# RamaTA.net
KiCad netlist of a schematic drawn in EAGLE
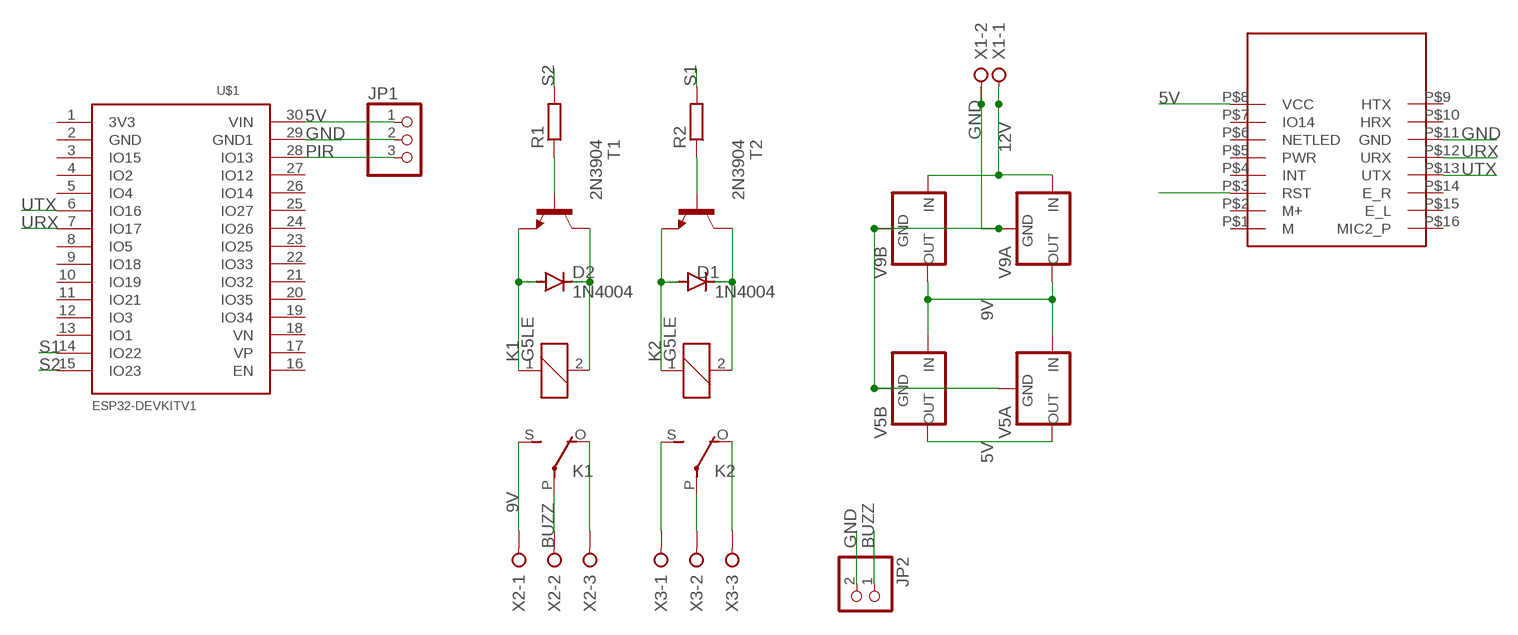
[diagram p0: schematic, sheet 1]

(export (version "E")
  (design (tool "Eeschema 10.0.6"))
  (components
    (comp (ref "D1")
      (value "1N4004")
      (footprint "eagle-import:DO41-10")
      (libsource (lib "eagle-import") (part "1N4004"))
    )
    (comp (ref "D2")
      (value "1N4004")
      (footprint "eagle-import:DO41-10")
      (libsource (lib "eagle-import") (part "1N4004"))
    )
    (comp (ref "JP1")
      (value "PINHD-1X3")
      (footprint "eagle-import:1X03")
      (libsource (lib "eagle-import") (part "PINHD-1X3"))
    )
    (comp (ref "JP2")
      (value "PINHD-1X2")
      (footprint "eagle-import:1X02")
      (libsource (lib "eagle-import") (part "PINHD-1X2"))
    )
    (comp (ref "K1")
      (value "G5LE")
      (footprint "eagle-import:G5LE")
      (libsource (lib "eagle-import") (part "G5LE"))
    )
    (comp (ref "K2")
      (value "G5LE")
      (footprint "eagle-import:G5LE")
      (libsource (lib "eagle-import") (part "G5LE"))
    )
    (comp (ref "R1")
      (value "R-EU_0207/10")
      (footprint "eagle-import:0207_10")
      (libsource (lib "eagle-import") (part "R-EU_0207/10"))
    )
    (comp (ref "R2")
      (value "R-EU_0207/10")
      (footprint "eagle-import:0207_10")
      (libsource (lib "eagle-import") (part "R-EU_0207/10"))
    )
    (comp (ref "T1")
      (value "2N3904")
      (footprint "eagle-import:TO92")
      (libsource (lib "eagle-import") (part "2N3904"))
    )
    (comp (ref "T2")
      (value "2N3904")
      (footprint "eagle-import:TO92")
      (libsource (lib "eagle-import") (part "2N3904"))
    )
    (comp (ref "U$1")
      (value "ESP32DEVKITV1")
      (footprint "eagle-import:ESP32-DEVKITV1")
      (libsource (lib "eagle-import") (part "ESP32DEVKITV1"))
    )
    (comp (ref "U$7")
      (value "SIM_A6SIM_GA6")
      (footprint "eagle-import:SIM_GA6")
      (libsource (lib "eagle-import") (part "SIM_A6SIM_GA6"))
    )
    (comp (ref "V5A")
      (value "78XXS")
      (footprint "eagle-import:78XXS")
      (libsource (lib "eagle-import") (part "78XXS"))
    )
    (comp (ref "V5B")
      (value "78XXS")
      (footprint "eagle-import:78XXS")
      (libsource (lib "eagle-import") (part "78XXS"))
    )
    (comp (ref "V9A")
      (value "78XXS")
      (footprint "eagle-import:78XXS")
      (libsource (lib "eagle-import") (part "78XXS"))
    )
    (comp (ref "V9B")
      (value "78XXS")
      (footprint "eagle-import:78XXS")
      (libsource (lib "eagle-import") (part "78XXS"))
    )
    (comp (ref "X1")
      (value "W237-02P")
      (footprint "eagle-import:W237-2")
      (libsource (lib "eagle-import") (part "W237-02P"))
    )
    (comp (ref "X2")
      (value "W237-03P")
      (footprint "eagle-import:W237-3")
      (libsource (lib "eagle-import") (part "W237-03P"))
    )
    (comp (ref "X3")
      (value "W237-03P")
      (footprint "eagle-import:W237-3")
      (libsource (lib "eagle-import") (part "W237-03P"))
    )
  )
  (nets
    (net (code "1") (name "/5V") (class "Default")
      (node (ref "JP1") (pin "1") (pinfunction "1_1") (pintype "passive"))
      (node (ref "U$1") (pin "30") (pinfunction "VIN_30") (pintype "bidirectional"))
      (node (ref "U$7") (pin "P$8") (pinfunction "VCC_P$8") (pintype "bidirectional"))
      (node (ref "V5A") (pin "OUT") (pinfunction "OUT_OUT") (pintype "passive"))
      (node (ref "V5B") (pin "OUT") (pinfunction "OUT_OUT") (pintype "passive"))
    )
    (net (code "2") (name "/9V") (class "Default")
      (node (ref "K1") (pin "S") (pinfunction "S_S") (pintype "passive"))
      (node (ref "V5A") (pin "IN") (pinfunction "IN_IN") (pintype "input"))
      (node (ref "V5B") (pin "IN") (pinfunction "IN_IN") (pintype "input"))
      (node (ref "V9A") (pin "OUT") (pinfunction "OUT_OUT") (pintype "passive"))
      (node (ref "V9B") (pin "OUT") (pinfunction "OUT_OUT") (pintype "passive"))
      (node (ref "X2") (pin "1") (pinfunction "KL_1") (pintype "passive"))
    )
    (net (code "3") (name "/12V") (class "Default")
      (node (ref "V9A") (pin "IN") (pinfunction "IN_IN") (pintype "input"))
      (node (ref "V9B") (pin "IN") (pinfunction "IN_IN") (pintype "input"))
      (node (ref "X1") (pin "1") (pinfunction "KL_1") (pintype "passive"))
    )
    (net (code "4") (name "/BUZZ") (class "Default")
      (node (ref "JP2") (pin "1") (pinfunction "1_1") (pintype "passive"))
      (node (ref "K1") (pin "P") (pinfunction "P_P") (pintype "passive"))
      (node (ref "X2") (pin "2") (pinfunction "KL_2") (pintype "passive"))
    )
    (net (code "5") (name "/GND") (class "Default")
      (node (ref "JP1") (pin "2") (pinfunction "2_2") (pintype "passive"))
      (node (ref "JP2") (pin "2") (pinfunction "2_2") (pintype "passive"))
      (node (ref "U$1") (pin "29") (pinfunction "GND1_29") (pintype "bidirectional"))
      (node (ref "U$7") (pin "P$11") (pinfunction "GND_P$11") (pintype "bidirectional"))
      (node (ref "V5A") (pin "GND") (pinfunction "GND_GND") (pintype "input"))
      (node (ref "V5B") (pin "GND") (pinfunction "GND_GND") (pintype "input"))
      (node (ref "V9A") (pin "GND") (pinfunction "GND_GND") (pintype "input"))
      (node (ref "V9B") (pin "GND") (pinfunction "GND_GND") (pintype "input"))
      (node (ref "X1") (pin "2") (pinfunction "KL_2") (pintype "passive"))
    )
    (net (code "6") (name "/PIR") (class "Default")
      (node (ref "JP1") (pin "3") (pinfunction "3_3") (pintype "passive"))
      (node (ref "U$1") (pin "28") (pinfunction "IO13_28") (pintype "bidirectional"))
    )
    (net (code "7") (name "/S1") (class "Default")
      (node (ref "R2") (pin "2") (pinfunction "2_2") (pintype "passive"))
      (node (ref "U$1") (pin "14") (pinfunction "IO22_14") (pintype "bidirectional"))
    )
    (net (code "8") (name "/S2") (class "Default")
      (node (ref "R1") (pin "2") (pinfunction "2_2") (pintype "passive"))
      (node (ref "U$1") (pin "15") (pinfunction "IO23_15") (pintype "bidirectional"))
    )
    (net (code "9") (name "/URX") (class "Default")
      (node (ref "U$1") (pin "7") (pinfunction "IO17_7") (pintype "bidirectional"))
      (node (ref "U$7") (pin "P$12") (pinfunction "URX_P$12") (pintype "bidirectional"))
    )
    (net (code "10") (name "/UTX") (class "Default")
      (node (ref "U$1") (pin "6") (pinfunction "IO16_6") (pintype "bidirectional"))
      (node (ref "U$7") (pin "P$13") (pinfunction "UTX_P$13") (pintype "bidirectional"))
    )
    (net (code "11") (name "Net-(T1-B)") (class "Default")
      (node (ref "R1") (pin "1") (pinfunction "1_1") (pintype "passive"))
      (node (ref "T1") (pin "2") (pinfunction "B_2") (pintype "passive"))
    )
    (net (code "12") (name "Net-(T1-C)") (class "Default")
      (node (ref "D2") (pin "C") (pinfunction "C_C") (pintype "passive"))
      (node (ref "K1") (pin "2") (pinfunction "2_2") (pintype "passive"))
      (node (ref "T1") (pin "1") (pinfunction "C_1") (pintype "passive"))
    )
    (net (code "13") (name "Net-(T1-E)") (class "Default")
      (node (ref "D2") (pin "A") (pinfunction "A_A") (pintype "passive"))
      (node (ref "K1") (pin "1") (pinfunction "1_1") (pintype "passive"))
      (node (ref "T1") (pin "3") (pinfunction "E_3") (pintype "passive"))
    )
    (net (code "14") (name "Net-(T2-B)") (class "Default")
      (node (ref "R2") (pin "1") (pinfunction "1_1") (pintype "passive"))
      (node (ref "T2") (pin "2") (pinfunction "B_2") (pintype "passive"))
    )
    (net (code "15") (name "Net-(T2-C)") (class "Default")
      (node (ref "D1") (pin "C") (pinfunction "C_C") (pintype "passive"))
      (node (ref "K2") (pin "2") (pinfunction "2_2") (pintype "passive"))
      (node (ref "T2") (pin "1") (pinfunction "C_1") (pintype "passive"))
    )
    (net (code "16") (name "Net-(T2-E)") (class "Default")
      (node (ref "D1") (pin "A") (pinfunction "A_A") (pintype "passive"))
      (node (ref "K2") (pin "1") (pinfunction "1_1") (pintype "passive"))
      (node (ref "T2") (pin "3") (pinfunction "E_3") (pintype "passive"))
    )
    (net (code "17") (name "Net-(X2C-KL)") (class "Default")
      (node (ref "K1") (pin "O") (pinfunction "O_O") (pintype "passive"))
      (node (ref "X2") (pin "3") (pinfunction "KL_3") (pintype "passive"))
    )
    (net (code "18") (name "Net-(X3A-KL)") (class "Default")
      (node (ref "K2") (pin "S") (pinfunction "S_S") (pintype "passive"))
      (node (ref "X3") (pin "1") (pinfunction "KL_1") (pintype "passive"))
    )
    (net (code "19") (name "Net-(X3B-KL)") (class "Default")
      (node (ref "K2") (pin "P") (pinfunction "P_P") (pintype "passive"))
      (node (ref "X3") (pin "2") (pinfunction "KL_2") (pintype "passive"))
    )
    (net (code "20") (name "Net-(X3C-KL)") (class "Default")
      (node (ref "K2") (pin "O") (pinfunction "O_O") (pintype "passive"))
      (node (ref "X3") (pin "3") (pinfunction "KL_3") (pintype "passive"))
    )
    (net (code "21") (name "unconnected-(U$1-3V3-Pad1)") (class "Default")
      (node (ref "U$1") (pin "1") (pinfunction "3V3_1") (pintype "bidirectional"))
    )
    (net (code "22") (name "unconnected-(U$1-EN-Pad16)") (class "Default")
      (node (ref "U$1") (pin "16") (pinfunction "EN_16") (pintype "bidirectional"))
    )
    (net (code "23") (name "unconnected-(U$1-GND-Pad2)") (class "Default")
      (node (ref "U$1") (pin "2") (pinfunction "GND_2") (pintype "bidirectional"))
    )
    (net (code "24") (name "unconnected-(U$1-IO1-Pad13)") (class "Default")
      (node (ref "U$1") (pin "13") (pinfunction "IO1_13") (pintype "bidirectional"))
    )
    (net (code "25") (name "unconnected-(U$1-IO2-Pad4)") (class "Default")
      (node (ref "U$1") (pin "4") (pinfunction "IO2_4") (pintype "bidirectional"))
    )
    (net (code "26") (name "unconnected-(U$1-IO3-Pad12)") (class "Default")
      (node (ref "U$1") (pin "12") (pinfunction "IO3_12") (pintype "bidirectional"))
    )
    (net (code "27") (name "unconnected-(U$1-IO4-Pad5)") (class "Default")
      (node (ref "U$1") (pin "5") (pinfunction "IO4_5") (pintype "bidirectional"))
    )
    (net (code "28") (name "unconnected-(U$1-IO5-Pad8)") (class "Default")
      (node (ref "U$1") (pin "8") (pinfunction "IO5_8") (pintype "bidirectional"))
    )
    (net (code "29") (name "unconnected-(U$1-IO12-Pad27)") (class "Default")
      (node (ref "U$1") (pin "27") (pinfunction "IO12_27") (pintype "bidirectional"))
    )
    (net (code "30") (name "unconnected-(U$1-IO14-Pad26)") (class "Default")
      (node (ref "U$1") (pin "26") (pinfunction "IO14_26") (pintype "bidirectional"))
    )
    (net (code "31") (name "unconnected-(U$1-IO15-Pad3)") (class "Default")
      (node (ref "U$1") (pin "3") (pinfunction "IO15_3") (pintype "bidirectional"))
    )
    (net (code "32") (name "unconnected-(U$1-IO18-Pad9)") (class "Default")
      (node (ref "U$1") (pin "9") (pinfunction "IO18_9") (pintype "bidirectional"))
    )
    (net (code "33") (name "unconnected-(U$1-IO19-Pad10)") (class "Default")
      (node (ref "U$1") (pin "10") (pinfunction "IO19_10") (pintype "bidirectional"))
    )
    (net (code "34") (name "unconnected-(U$1-IO21-Pad11)") (class "Default")
      (node (ref "U$1") (pin "11") (pinfunction "IO21_11") (pintype "bidirectional"))
    )
    (net (code "35") (name "unconnected-(U$1-IO25-Pad23)") (class "Default")
      (node (ref "U$1") (pin "23") (pinfunction "IO25_23") (pintype "bidirectional"))
    )
    (net (code "36") (name "unconnected-(U$1-IO26-Pad24)") (class "Default")
      (node (ref "U$1") (pin "24") (pinfunction "IO26_24") (pintype "bidirectional"))
    )
    (net (code "37") (name "unconnected-(U$1-IO27-Pad25)") (class "Default")
      (node (ref "U$1") (pin "25") (pinfunction "IO27_25") (pintype "bidirectional"))
    )
    (net (code "38") (name "unconnected-(U$1-IO32-Pad21)") (class "Default")
      (node (ref "U$1") (pin "21") (pinfunction "IO32_21") (pintype "bidirectional"))
    )
    (net (code "39") (name "unconnected-(U$1-IO33-Pad22)") (class "Default")
      (node (ref "U$1") (pin "22") (pinfunction "IO33_22") (pintype "bidirectional"))
    )
    (net (code "40") (name "unconnected-(U$1-IO34-Pad19)") (class "Default")
      (node (ref "U$1") (pin "19") (pinfunction "IO34_19") (pintype "bidirectional"))
    )
    (net (code "41") (name "unconnected-(U$1-IO35-Pad20)") (class "Default")
      (node (ref "U$1") (pin "20") (pinfunction "IO35_20") (pintype "bidirectional"))
    )
    (net (code "42") (name "unconnected-(U$1-VN-Pad18)") (class "Default")
      (node (ref "U$1") (pin "18") (pinfunction "VN_18") (pintype "bidirectional"))
    )
    (net (code "43") (name "unconnected-(U$1-VP-Pad17)") (class "Default")
      (node (ref "U$1") (pin "17") (pinfunction "VP_17") (pintype "bidirectional"))
    )
    (net (code "44") (name "unconnected-(U$7-E_L-PadP$15)") (class "Default")
      (node (ref "U$7") (pin "P$15") (pinfunction "E_L_P$15") (pintype "bidirectional"))
    )
    (net (code "45") (name "unconnected-(U$7-E_R-PadP$14)") (class "Default")
      (node (ref "U$7") (pin "P$14") (pinfunction "E_R_P$14") (pintype "bidirectional"))
    )
    (net (code "46") (name "unconnected-(U$7-HRX-PadP$10)") (class "Default")
      (node (ref "U$7") (pin "P$10") (pinfunction "HRX_P$10") (pintype "bidirectional"))
    )
    (net (code "47") (name "unconnected-(U$7-HTX-PadP$9)") (class "Default")
      (node (ref "U$7") (pin "P$9") (pinfunction "HTX_P$9") (pintype "bidirectional"))
    )
    (net (code "48") (name "unconnected-(U$7-INT-PadP$4)") (class "Default")
      (node (ref "U$7") (pin "P$4") (pinfunction "INT_P$4") (pintype "bidirectional"))
    )
    (net (code "49") (name "unconnected-(U$7-IO14-PadP$7)") (class "Default")
      (node (ref "U$7") (pin "P$7") (pinfunction "IO14_P$7") (pintype "bidirectional"))
    )
    (net (code "50") (name "unconnected-(U$7-M+-PadP$2)") (class "Default")
      (node (ref "U$7") (pin "P$2") (pinfunction "M+_P$2") (pintype "bidirectional"))
    )
    (net (code "51") (name "unconnected-(U$7-M-PadP$1)") (class "Default")
      (node (ref "U$7") (pin "P$1") (pinfunction "M_P$1") (pintype "bidirectional"))
    )
    (net (code "52") (name "unconnected-(U$7-MIC2_P-PadP$16)") (class "Default")
      (node (ref "U$7") (pin "P$16") (pinfunction "MIC2_P_P$16") (pintype "bidirectional"))
    )
    (net (code "53") (name "unconnected-(U$7-NETLED-PadP$6)") (class "Default")
      (node (ref "U$7") (pin "P$6") (pinfunction "NETLED_P$6") (pintype "bidirectional"))
    )
    (net (code "54") (name "unconnected-(U$7-PWR-PadP$5)") (class "Default")
      (node (ref "U$7") (pin "P$5") (pinfunction "PWR_P$5") (pintype "bidirectional"))
    )
    (net (code "55") (name "unconnected-(U$7-RST-PadP$3)") (class "Default")
      (node (ref "U$7") (pin "P$3") (pinfunction "RST_P$3") (pintype "bidirectional"))
    )
  )
)
